# dacOut.net
KiCad netlist of a schematic drawn in Altium Designer
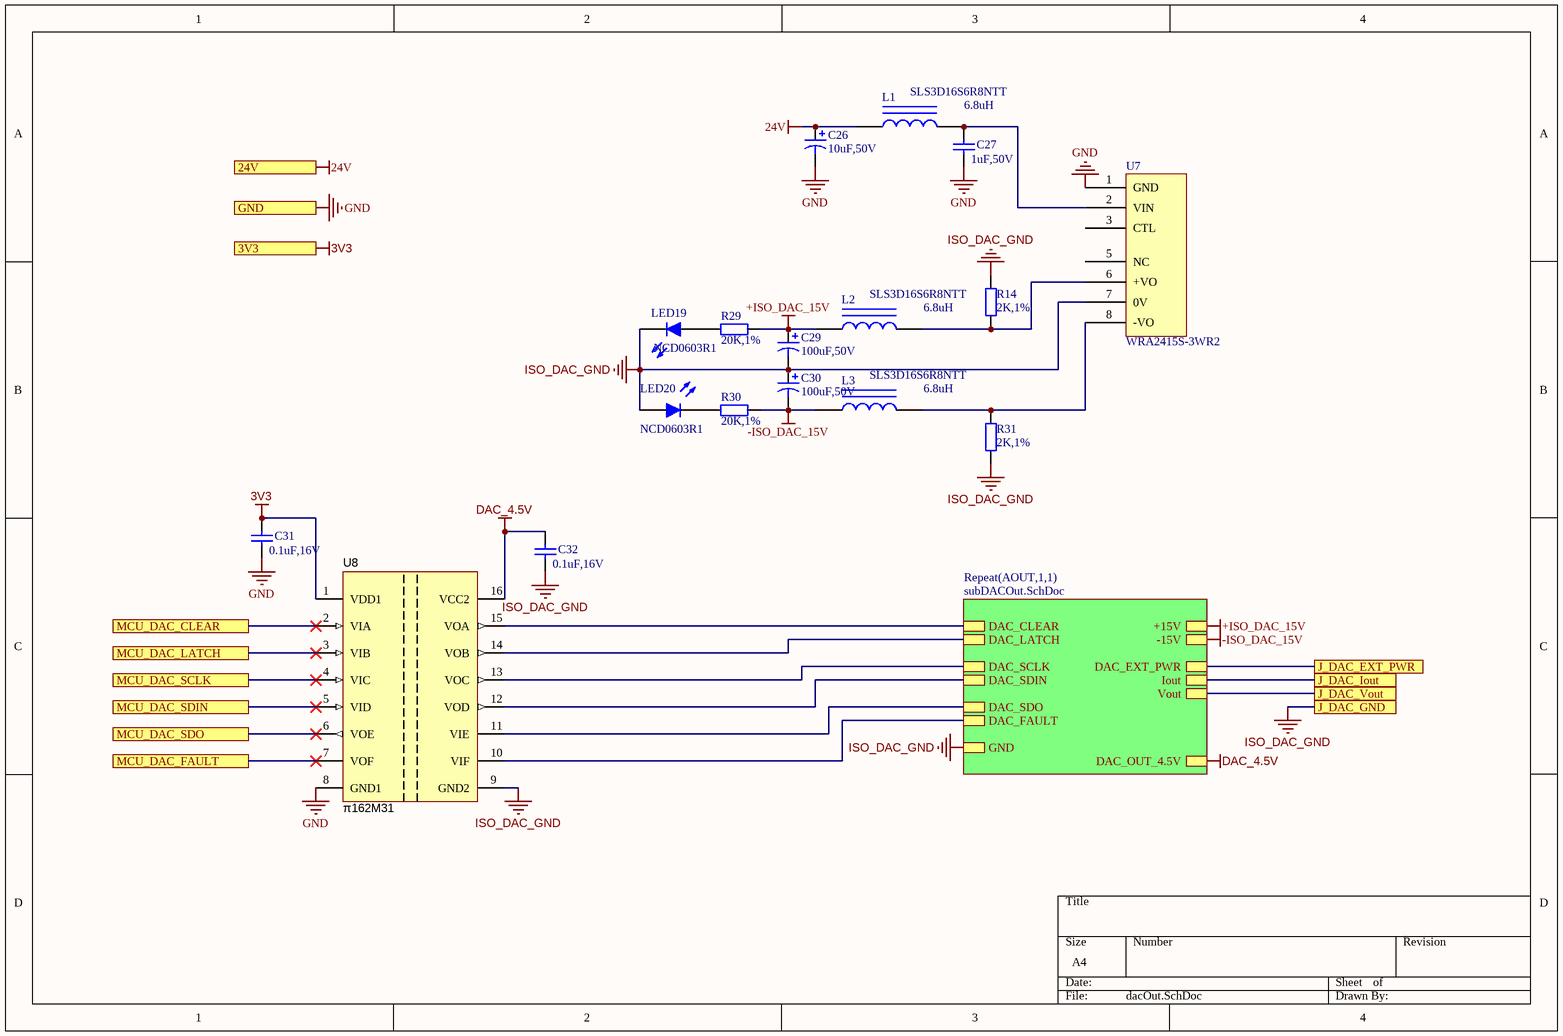
[diagram p0: dacOut.SchDoc]

(export (version "E")
  (design (tool "Eeschema 10.0.6"))
  (components
    (comp (ref "C26")
      (value "10uF,50V")
      (footprint "CAP-TH_BD5.0-P2.00-D0.8-FD")
      (description "有极电容")
      (libsource (lib "散件") (part "有极电容"))
    )
    (comp (ref "C27")
      (value "1uF,50V")
      (footprint "C0603")
      (description "无极电容")
      (libsource (lib "电阻电容") (part "无极电容"))
    )
    (comp (ref "C29")
      (value "100uF,50V")
      (footprint "CAP-TH_BD6.3-P2.50-D1.0-FD")
      (description "有极电容")
      (libsource (lib "散件") (part "有极电容"))
    )
    (comp (ref "C30")
      (value "100uF,50V")
      (footprint "CAP-TH_BD6.3-P2.50-D1.0-FD")
      (description "有极电容")
      (libsource (lib "散件") (part "有极电容"))
    )
    (comp (ref "C31")
      (value "0.1uF,16V")
      (footprint "C0603")
      (description "无极电容")
      (libsource (lib "电阻电容") (part "无极电容"))
    )
    (comp (ref "C32")
      (value "0.1uF,16V")
      (footprint "C0603")
      (description "无极电容")
      (libsource (lib "电阻电容") (part "无极电容"))
    )
    (comp (ref "L1")
      (value "SLS3D16S6R8NTT")
      (footprint "IND-SMD_L4.0-W4.0_SLS3DXX")
      (description "Magnetic-Core Inductor")
      (fields (field (name "ALTIUM_VALUE") "6.8uH") (field (name "PUBLISHER") "Altium Limited"))
      (libsource (lib "Miscellaneous Devices") (part "Inductor Iron"))
    )
    (comp (ref "L2")
      (value "SLS3D16S6R8NTT")
      (footprint "IND-SMD_L4.0-W4.0_SLS3DXX")
      (description "Magnetic-Core Inductor")
      (fields (field (name "ALTIUM_VALUE") "6.8uH") (field (name "PUBLISHER") "Altium Limited"))
      (libsource (lib "Miscellaneous Devices") (part "Inductor Iron"))
    )
    (comp (ref "L3")
      (value "SLS3D16S6R8NTT")
      (footprint "IND-SMD_L4.0-W4.0_SLS3DXX")
      (description "Magnetic-Core Inductor")
      (fields (field (name "ALTIUM_VALUE") "6.8uH") (field (name "PUBLISHER") "Altium Limited"))
      (libsource (lib "Miscellaneous Devices") (part "Inductor Iron"))
    )
    (comp (ref "LED19")
      (value "NCD0603R1")
      (footprint "LED0603-RD")
      (description "Typical INFRARED GaAs LED")
      (libsource (lib "Schlib1") (part "LED0603"))
    )
    (comp (ref "LED20")
      (value "NCD0603R1")
      (footprint "LED0603-RD")
      (description "Typical INFRARED GaAs LED")
      (libsource (lib "Schlib1") (part "LED0603"))
    )
    (comp (ref "R14")
      (value "2K,1%")
      (footprint "R0603")
      (description "电阻")
      (libsource (lib "") (part "电阻_1"))
    )
    (comp (ref "R29")
      (value "20K,1%")
      (footprint "R0603")
      (description "电阻")
      (libsource (lib "电阻电容") (part "电阻"))
    )
    (comp (ref "R30")
      (value "20K,1%")
      (footprint "R0603")
      (description "电阻")
      (libsource (lib "电阻电容") (part "电阻"))
    )
    (comp (ref "R31")
      (value "2K,1%")
      (footprint "R0603")
      (description "电阻")
      (libsource (lib "") (part "电阻_1"))
    )
    (comp (ref "U7")
      (value "WRA2415S-3WR2")
      (footprint "PWRM-TH_WRA2415S-3WR2")
      (description "3W，宽电压输入，隔离稳压正负双路/单路输出 DC/DC 模块电源")
      (libsource (lib "Schlib1") (part "WRA2415S-3WR2"))
    )
    (comp (ref "U8")
      (value "π162M31")
      (footprint "SOIC-16_L9.9-W3.9-P1.27-LS6.0-BL")
      (description "Robust EMC, Low Power, 4 Out Channel, 2 Input Channel Digital Isolators.")
      (libsource (lib "Schlib1") (part "π162M31"))
    )
  )
  (nets
    (net (code "1") (name "+ISO_DAC_15V") (class "Default")
      (node (ref "C29") (pin "1") (pinfunction "1_1") (pintype "passive"))
      (node (ref "L2") (pin "1") (pinfunction "1_1") (pintype "passive"))
      (node (ref "R29") (pin "2") (pinfunction "2_2") (pintype "passive"))
    )
    (net (code "2") (name "-ISO_DAC_15V") (class "Default")
      (node (ref "C30") (pin "2") (pinfunction "2_2") (pintype "passive"))
      (node (ref "L3") (pin "1") (pinfunction "1_1") (pintype "passive"))
      (node (ref "R30") (pin "2") (pinfunction "2_2") (pintype "passive"))
    )
    (net (code "3") (name "/DAC_CLEAR") (class "Default")
      (node (ref "U8") (pin "15") (pinfunction "VOA_15") (pintype "output"))
    )
    (net (code "4") (name "/DAC_FAULT") (class "Default")
      (node (ref "U8") (pin "10") (pinfunction "VIF_10") (pintype "power_in"))
    )
    (net (code "5") (name "/DAC_LATCH") (class "Default")
      (node (ref "U8") (pin "14") (pinfunction "VOB_14") (pintype "output"))
    )
    (net (code "6") (name "/DAC_SCLK") (class "Default")
      (node (ref "U8") (pin "13") (pinfunction "VOC_13") (pintype "output"))
    )
    (net (code "7") (name "/DAC_SDIN") (class "Default")
      (node (ref "U8") (pin "12") (pinfunction "VOD_12") (pintype "output"))
    )
    (net (code "8") (name "/DAC_SDO") (class "Default")
      (node (ref "U8") (pin "11") (pinfunction "VIE_11") (pintype "passive"))
    )
    (net (code "12") (name "/MCU_DAC_CLEAR") (class "Default")
      (node (ref "U8") (pin "2") (pinfunction "VIA_2") (pintype "input+no_connect"))
    )
    (net (code "13") (name "/MCU_DAC_FAULT") (class "Default")
      (node (ref "U8") (pin "7") (pinfunction "VOF_7") (pintype "power_in+no_connect"))
    )
    (net (code "14") (name "/MCU_DAC_LATCH") (class "Default")
      (node (ref "U8") (pin "3") (pinfunction "VIB_3") (pintype "input+no_connect"))
    )
    (net (code "15") (name "/MCU_DAC_SCLK") (class "Default")
      (node (ref "U8") (pin "4") (pinfunction "VIC_4") (pintype "input+no_connect"))
    )
    (net (code "16") (name "/MCU_DAC_SDIN") (class "Default")
      (node (ref "U8") (pin "5") (pinfunction "VID_5") (pintype "input+no_connect"))
    )
    (net (code "17") (name "/MCU_DAC_SDO") (class "Default")
      (node (ref "U8") (pin "6") (pinfunction "VOE_6") (pintype "output+no_connect"))
    )
    (net (code "18") (name "3V3") (class "Default")
      (node (ref "C31") (pin "2") (pinfunction "2_2") (pintype "passive"))
      (node (ref "U8") (pin "1") (pinfunction "VDD1_1") (pintype "power_in"))
    )
    (net (code "19") (name "24V") (class "Default")
      (node (ref "C26") (pin "1") (pinfunction "1_1") (pintype "passive"))
      (node (ref "L1") (pin "1") (pinfunction "1_1") (pintype "passive"))
    )
    (net (code "20") (name "DAC_4.5V") (class "Default")
      (node (ref "C32") (pin "2") (pinfunction "2_2") (pintype "passive"))
      (node (ref "U8") (pin "16") (pinfunction "VCC2_16") (pintype "power_in"))
    )
    (net (code "21") (name "GND") (class "Default")
      (node (ref "C26") (pin "2") (pinfunction "2_2") (pintype "passive"))
      (node (ref "C27") (pin "1") (pinfunction "1_1") (pintype "passive"))
      (node (ref "C31") (pin "1") (pinfunction "1_1") (pintype "passive"))
      (node (ref "U7") (pin "1") (pinfunction "GND_1") (pintype "passive"))
      (node (ref "U8") (pin "8") (pinfunction "GND1_8") (pintype "power_in"))
    )
    (net (code "22") (name "ISO_DAC_GND") (class "Default")
      (node (ref "C29") (pin "2") (pinfunction "2_2") (pintype "passive"))
      (node (ref "C30") (pin "1") (pinfunction "1_1") (pintype "passive"))
      (node (ref "C32") (pin "1") (pinfunction "1_1") (pintype "passive"))
      (node (ref "LED19") (pin "1") (pinfunction "K_1") (pintype "passive"))
      (node (ref "LED20") (pin "2") (pinfunction "A_2") (pintype "passive"))
      (node (ref "R14") (pin "2") (pinfunction "2_2") (pintype "passive"))
      (node (ref "R31") (pin "1") (pinfunction "1_1") (pintype "passive"))
      (node (ref "U7") (pin "7") (pinfunction "0V_7") (pintype "passive"))
      (node (ref "U8") (pin "9") (pinfunction "GND2_9") (pintype "power_in"))
    )
    (net (code "23") (name "Net-(LED19-A)") (class "Default")
      (node (ref "LED19") (pin "2") (pinfunction "A_2") (pintype "passive"))
      (node (ref "R29") (pin "1") (pinfunction "1_1") (pintype "passive"))
    )
    (net (code "24") (name "Net-(LED20-K)") (class "Default")
      (node (ref "LED20") (pin "1") (pinfunction "K_1") (pintype "passive"))
      (node (ref "R30") (pin "1") (pinfunction "1_1") (pintype "passive"))
    )
    (net (code "25") (name "Net-(U7-+VO)") (class "Default")
      (node (ref "L2") (pin "2") (pinfunction "2_2") (pintype "passive"))
      (node (ref "R14") (pin "1") (pinfunction "1_1") (pintype "passive"))
      (node (ref "U7") (pin "6") (pinfunction "+VO_6") (pintype "passive"))
    )
    (net (code "26") (name "Net-(U7--VO)") (class "Default")
      (node (ref "L3") (pin "2") (pinfunction "2_2") (pintype "passive"))
      (node (ref "R31") (pin "2") (pinfunction "2_2") (pintype "passive"))
      (node (ref "U7") (pin "8") (pinfunction "-VO_8") (pintype "passive"))
    )
    (net (code "27") (name "Net-(U7-VIN)") (class "Default")
      (node (ref "C27") (pin "2") (pinfunction "2_2") (pintype "passive"))
      (node (ref "L1") (pin "2") (pinfunction "2_2") (pintype "passive"))
      (node (ref "U7") (pin "2") (pinfunction "VIN_2") (pintype "passive"))
    )
    (net (code "28") (name "unconnected-(U7-CTL-Pad3)") (class "Default")
      (node (ref "U7") (pin "3") (pinfunction "CTL_3") (pintype "passive"))
    )
    (net (code "29") (name "unconnected-(U7-NC-Pad5)") (class "Default")
      (node (ref "U7") (pin "5") (pinfunction "NC_5") (pintype "passive"))
    )
  )
)
